# 07_LMS7002M_Power.net
KiCad netlist of a schematic drawn in Altium Designer
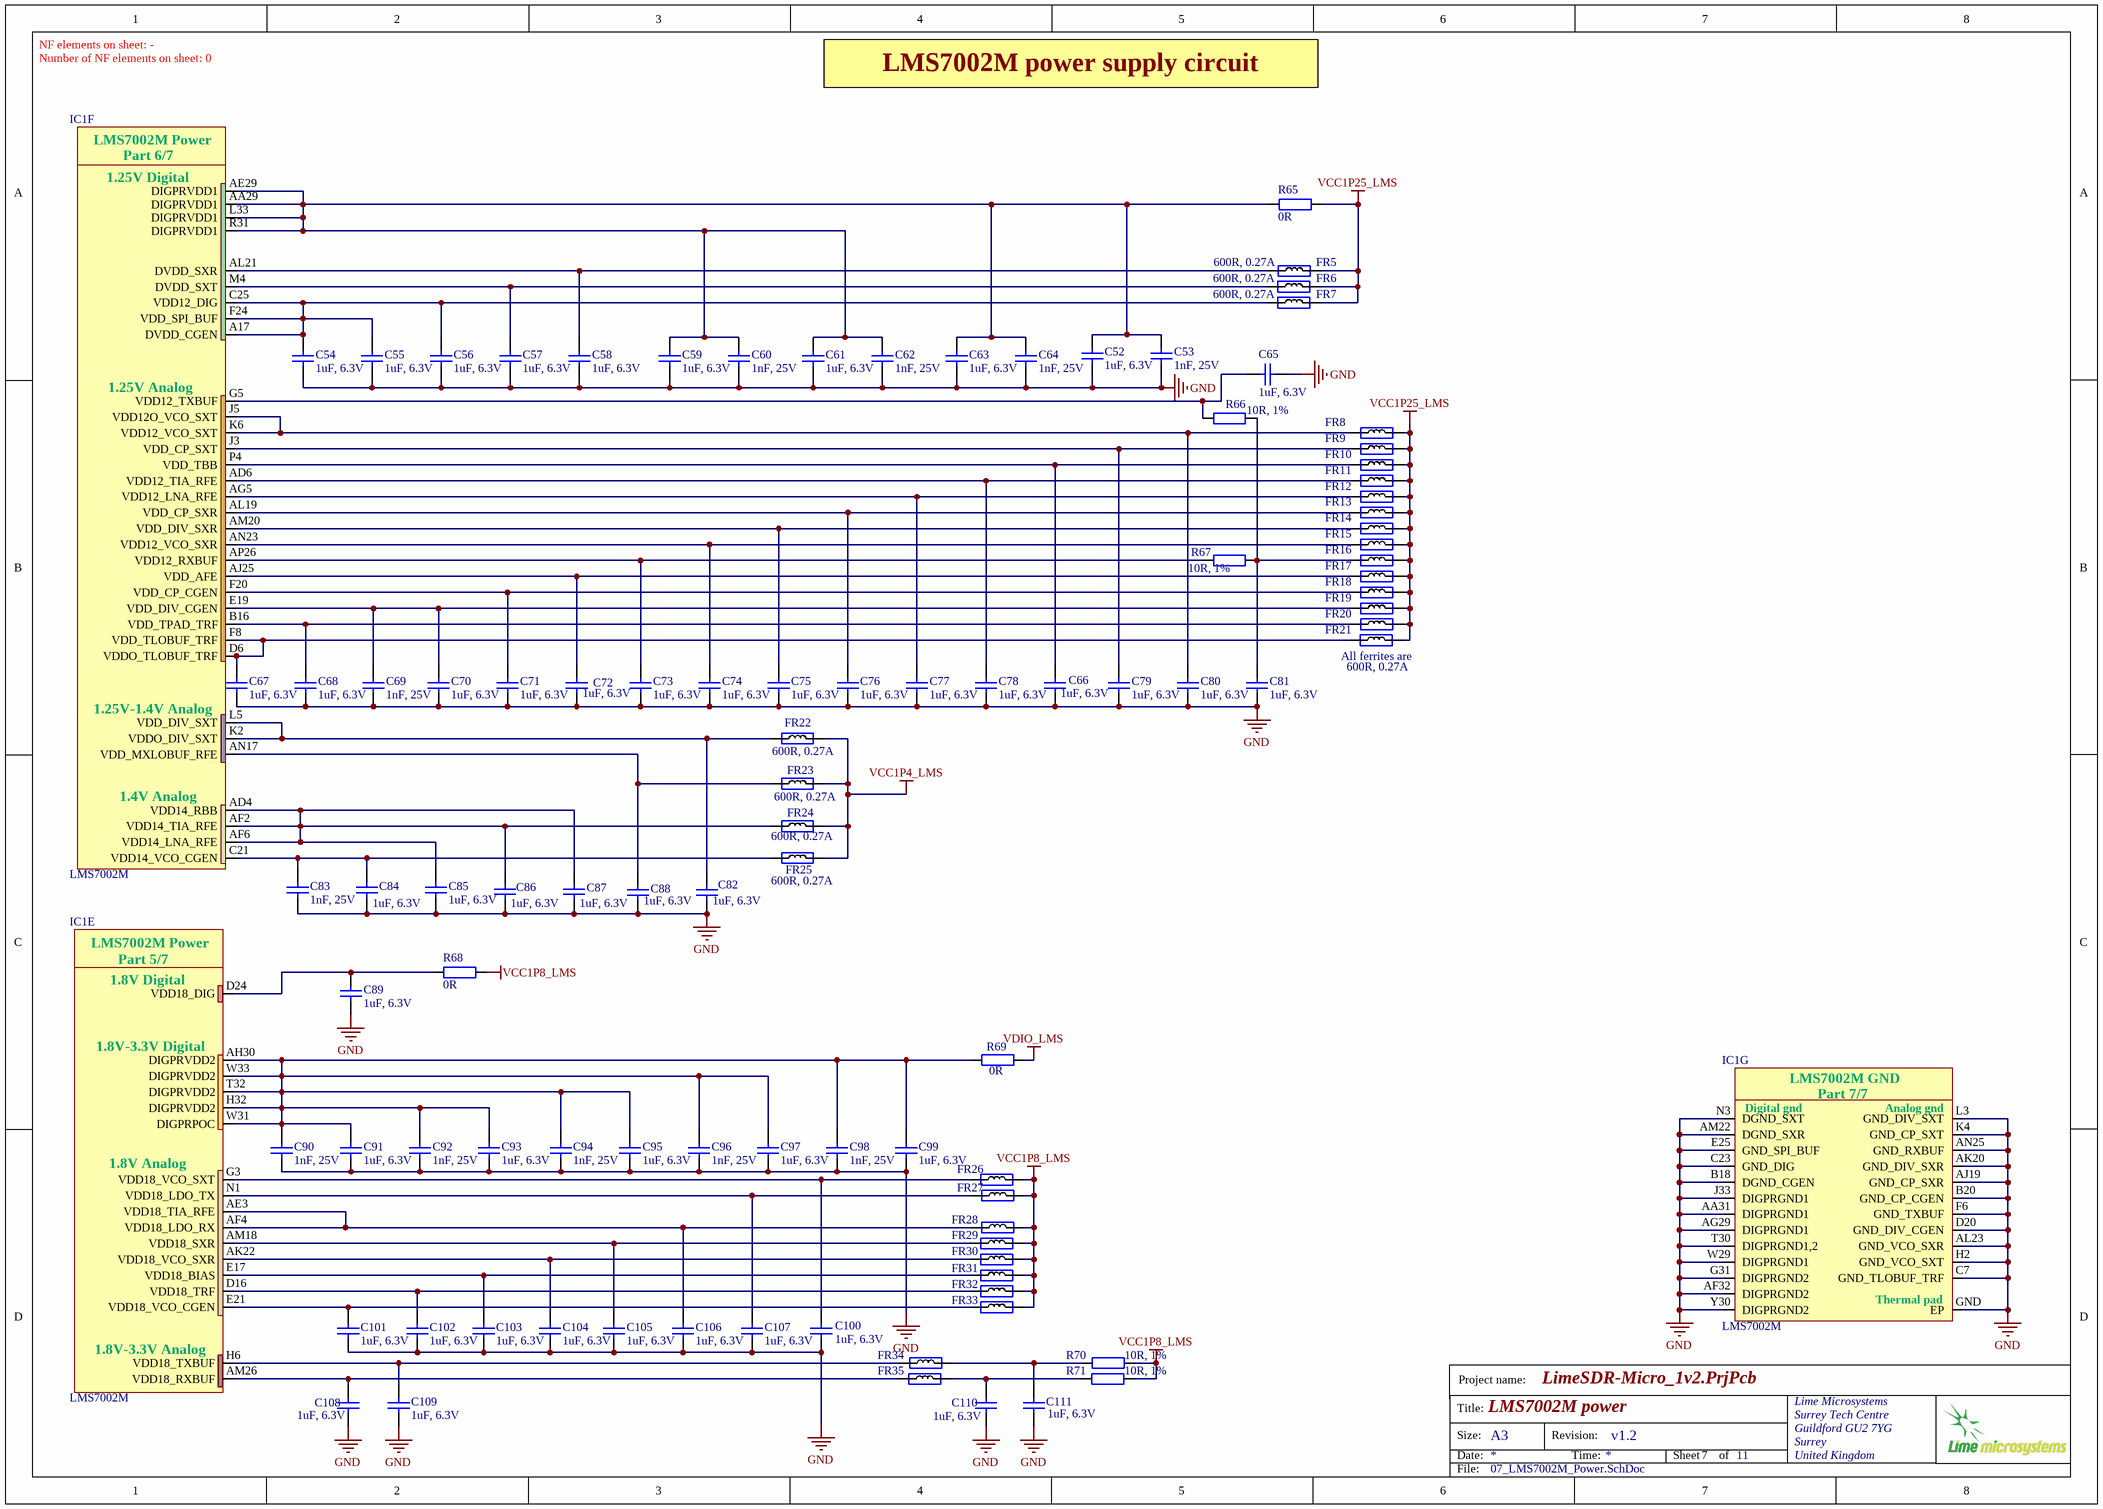
[diagram p0: 07_LMS7002M_Power.SchDoc]

(export (version "E")
  (design (tool "Eeschema 10.0.6"))
  (components
    (comp (ref "C52")
      (value "1uF, 6.3V")
      (footprint "CAP0201")
      (fields (field (name "TOLERANCE") "±20%") (field (name "MANUFACTURER") "TDK Corporation"))
      (libsource (lib "LimeMicroAltiumLib_schLib") (part "Cap_0402"))
    )
    (comp (ref "C53")
      (value "1nF, 25V")
      (footprint "CAP0201")
      (fields (field (name "TOLERANCE") "±10%") (field (name "MANUFACTURER") "TDK Corporation"))
      (libsource (lib "LimeMicroAltiumLib_schLib") (part "Cap_0402"))
    )
    (comp (ref "C54")
      (value "1uF, 6.3V")
      (footprint "CAP0201")
      (fields (field (name "TOLERANCE") "±20%") (field (name "MANUFACTURER") "TDK Corporation"))
      (libsource (lib "LimeMicroAltiumLib_schLib") (part "Cap_0402"))
    )
    (comp (ref "C55")
      (value "1uF, 6.3V")
      (footprint "CAP0201")
      (fields (field (name "TOLERANCE") "±20%") (field (name "MANUFACTURER") "TDK Corporation"))
      (libsource (lib "LimeMicroAltiumLib_schLib") (part "Cap_0402"))
    )
    (comp (ref "C56")
      (value "1uF, 6.3V")
      (footprint "CAP0201")
      (fields (field (name "TOLERANCE") "±20%") (field (name "MANUFACTURER") "TDK Corporation"))
      (libsource (lib "LimeMicroAltiumLib_schLib") (part "Cap_0402"))
    )
    (comp (ref "C57")
      (value "1uF, 6.3V")
      (footprint "CAP0201")
      (fields (field (name "TOLERANCE") "±20%") (field (name "MANUFACTURER") "TDK Corporation"))
      (libsource (lib "LimeMicroAltiumLib_schLib") (part "Cap_0402"))
    )
    (comp (ref "C58")
      (value "1uF, 6.3V")
      (footprint "CAP0201")
      (fields (field (name "TOLERANCE") "±20%") (field (name "MANUFACTURER") "TDK Corporation"))
      (libsource (lib "LimeMicroAltiumLib_schLib") (part "Cap_0402"))
    )
    (comp (ref "C59")
      (value "1uF, 6.3V")
      (footprint "CAP0201")
      (fields (field (name "TOLERANCE") "±20%") (field (name "MANUFACTURER") "TDK Corporation"))
      (libsource (lib "LimeMicroAltiumLib_schLib") (part "Cap_0402"))
    )
    (comp (ref "C60")
      (value "1nF, 25V")
      (footprint "CAP0201")
      (fields (field (name "TOLERANCE") "±10%") (field (name "MANUFACTURER") "TDK Corporation"))
      (libsource (lib "LimeMicroAltiumLib_schLib") (part "Cap_0402"))
    )
    (comp (ref "C61")
      (value "1uF, 6.3V")
      (footprint "CAP0201")
      (fields (field (name "TOLERANCE") "±20%") (field (name "MANUFACTURER") "TDK Corporation"))
      (libsource (lib "LimeMicroAltiumLib_schLib") (part "Cap_0402"))
    )
    (comp (ref "C62")
      (value "1nF, 25V")
      (footprint "CAP0201")
      (fields (field (name "TOLERANCE") "±10%") (field (name "MANUFACTURER") "TDK Corporation"))
      (libsource (lib "LimeMicroAltiumLib_schLib") (part "Cap_0402"))
    )
    (comp (ref "C63")
      (value "1uF, 6.3V")
      (footprint "CAP0201")
      (fields (field (name "TOLERANCE") "±20%") (field (name "MANUFACTURER") "TDK Corporation"))
      (libsource (lib "LimeMicroAltiumLib_schLib") (part "Cap_0402"))
    )
    (comp (ref "C64")
      (value "1nF, 25V")
      (footprint "CAP0201")
      (fields (field (name "TOLERANCE") "±10%") (field (name "MANUFACTURER") "TDK Corporation"))
      (libsource (lib "LimeMicroAltiumLib_schLib") (part "Cap_0402"))
    )
    (comp (ref "C65")
      (value "1uF, 6.3V")
      (footprint "CAP0201")
      (fields (field (name "TOLERANCE") "±20%") (field (name "MANUFACTURER") "TDK Corporation"))
      (libsource (lib "LimeMicroAltiumLib_schLib") (part "Cap_0402"))
    )
    (comp (ref "C66")
      (value "1uF, 6.3V")
      (footprint "CAP0201")
      (fields (field (name "TOLERANCE") "±20%") (field (name "MANUFACTURER") "TDK Corporation"))
      (libsource (lib "LimeMicroAltiumLib_schLib") (part "Cap_0402"))
    )
    (comp (ref "C67")
      (value "1uF, 6.3V")
      (footprint "CAP0201")
      (fields (field (name "TOLERANCE") "±20%") (field (name "MANUFACTURER") "TDK Corporation"))
      (libsource (lib "LimeMicroAltiumLib_schLib") (part "Cap_0402"))
    )
    (comp (ref "C68")
      (value "1uF, 6.3V")
      (footprint "CAP0201")
      (fields (field (name "TOLERANCE") "±20%") (field (name "MANUFACTURER") "TDK Corporation"))
      (libsource (lib "LimeMicroAltiumLib_schLib") (part "Cap_0402"))
    )
    (comp (ref "C69")
      (value "1nF, 25V")
      (footprint "CAP0201")
      (fields (field (name "TOLERANCE") "±10%") (field (name "MANUFACTURER") "TDK Corporation"))
      (libsource (lib "LimeMicroAltiumLib_schLib") (part "Cap_0402"))
    )
    (comp (ref "C70")
      (value "1uF, 6.3V")
      (footprint "CAP0201")
      (fields (field (name "TOLERANCE") "±20%") (field (name "MANUFACTURER") "TDK Corporation"))
      (libsource (lib "LimeMicroAltiumLib_schLib") (part "Cap_0402"))
    )
    (comp (ref "C71")
      (value "1uF, 6.3V")
      (footprint "CAP0201")
      (fields (field (name "TOLERANCE") "±20%") (field (name "MANUFACTURER") "TDK Corporation"))
      (libsource (lib "LimeMicroAltiumLib_schLib") (part "Cap_0402"))
    )
    (comp (ref "C72")
      (value "1uF, 6.3V")
      (footprint "CAP0201")
      (fields (field (name "TOLERANCE") "±20%") (field (name "MANUFACTURER") "TDK Corporation"))
      (libsource (lib "LimeMicroAltiumLib_schLib") (part "Cap_0402"))
    )
    (comp (ref "C73")
      (value "1uF, 6.3V")
      (footprint "CAP0201")
      (fields (field (name "TOLERANCE") "±20%") (field (name "MANUFACTURER") "TDK Corporation"))
      (libsource (lib "LimeMicroAltiumLib_schLib") (part "Cap_0402"))
    )
    (comp (ref "C74")
      (value "1uF, 6.3V")
      (footprint "CAP0201")
      (fields (field (name "TOLERANCE") "±20%") (field (name "MANUFACTURER") "TDK Corporation"))
      (libsource (lib "LimeMicroAltiumLib_schLib") (part "Cap_0402"))
    )
    (comp (ref "C75")
      (value "1uF, 6.3V")
      (footprint "CAP0201")
      (fields (field (name "TOLERANCE") "±20%") (field (name "MANUFACTURER") "TDK Corporation"))
      (libsource (lib "LimeMicroAltiumLib_schLib") (part "Cap_0402"))
    )
    (comp (ref "C76")
      (value "1uF, 6.3V")
      (footprint "CAP0201")
      (fields (field (name "TOLERANCE") "±20%") (field (name "MANUFACTURER") "TDK Corporation"))
      (libsource (lib "LimeMicroAltiumLib_schLib") (part "Cap_0402"))
    )
    (comp (ref "C77")
      (value "1uF, 6.3V")
      (footprint "CAP0201")
      (fields (field (name "TOLERANCE") "±20%") (field (name "MANUFACTURER") "TDK Corporation"))
      (libsource (lib "LimeMicroAltiumLib_schLib") (part "Cap_0402"))
    )
    (comp (ref "C78")
      (value "1uF, 6.3V")
      (footprint "CAP0201")
      (fields (field (name "TOLERANCE") "±20%") (field (name "MANUFACTURER") "TDK Corporation"))
      (libsource (lib "LimeMicroAltiumLib_schLib") (part "Cap_0402"))
    )
    (comp (ref "C79")
      (value "1uF, 6.3V")
      (footprint "CAP0201")
      (fields (field (name "TOLERANCE") "±20%") (field (name "MANUFACTURER") "TDK Corporation"))
      (libsource (lib "LimeMicroAltiumLib_schLib") (part "Cap_0402"))
    )
    (comp (ref "C80")
      (value "1uF, 6.3V")
      (footprint "CAP0201")
      (fields (field (name "TOLERANCE") "±20%") (field (name "MANUFACTURER") "TDK Corporation"))
      (libsource (lib "LimeMicroAltiumLib_schLib") (part "Cap_0402"))
    )
    (comp (ref "C81")
      (value "1uF, 6.3V")
      (footprint "CAP0201")
      (fields (field (name "TOLERANCE") "±20%") (field (name "MANUFACTURER") "TDK Corporation"))
      (libsource (lib "LimeMicroAltiumLib_schLib") (part "Cap_0402"))
    )
    (comp (ref "C82")
      (value "1uF, 6.3V")
      (footprint "CAP0201")
      (fields (field (name "TOLERANCE") "±20%") (field (name "MANUFACTURER") "TDK Corporation"))
      (libsource (lib "LimeMicroAltiumLib_schLib") (part "Cap_0402"))
    )
    (comp (ref "C83")
      (value "1nF, 25V")
      (footprint "CAP0201")
      (fields (field (name "TOLERANCE") "±10%") (field (name "MANUFACTURER") "TDK Corporation"))
      (libsource (lib "LimeMicroAltiumLib_schLib") (part "Cap_0402"))
    )
    (comp (ref "C84")
      (value "1uF, 6.3V")
      (footprint "CAP0201")
      (fields (field (name "TOLERANCE") "±20%") (field (name "MANUFACTURER") "TDK Corporation"))
      (libsource (lib "LimeMicroAltiumLib_schLib") (part "Cap_0402"))
    )
    (comp (ref "C85")
      (value "1uF, 6.3V")
      (footprint "CAP0201")
      (fields (field (name "TOLERANCE") "±20%") (field (name "MANUFACTURER") "TDK Corporation"))
      (libsource (lib "LimeMicroAltiumLib_schLib") (part "Cap_0402"))
    )
    (comp (ref "C86")
      (value "1uF, 6.3V")
      (footprint "CAP0201")
      (fields (field (name "TOLERANCE") "±20%") (field (name "MANUFACTURER") "TDK Corporation"))
      (libsource (lib "LimeMicroAltiumLib_schLib") (part "Cap_0402"))
    )
    (comp (ref "C87")
      (value "1uF, 6.3V")
      (footprint "CAP0201")
      (fields (field (name "TOLERANCE") "±20%") (field (name "MANUFACTURER") "TDK Corporation"))
      (libsource (lib "LimeMicroAltiumLib_schLib") (part "Cap_0402"))
    )
    (comp (ref "C88")
      (value "1uF, 6.3V")
      (footprint "CAP0201")
      (fields (field (name "TOLERANCE") "±20%") (field (name "MANUFACTURER") "TDK Corporation"))
      (libsource (lib "LimeMicroAltiumLib_schLib") (part "Cap_0402"))
    )
    (comp (ref "C89")
      (value "1uF, 6.3V")
      (footprint "CAP0201")
      (fields (field (name "TOLERANCE") "±20%") (field (name "MANUFACTURER") "TDK Corporation"))
      (libsource (lib "LimeMicroAltiumLib_schLib") (part "Cap_0402"))
    )
    (comp (ref "C90")
      (value "1nF, 25V")
      (footprint "CAP0201")
      (fields (field (name "TOLERANCE") "±10%") (field (name "MANUFACTURER") "TDK Corporation"))
      (libsource (lib "LimeMicroAltiumLib_schLib") (part "Cap_0402"))
    )
    (comp (ref "C91")
      (value "1uF, 6.3V")
      (footprint "CAP0201")
      (fields (field (name "TOLERANCE") "±20%") (field (name "MANUFACTURER") "TDK Corporation"))
      (libsource (lib "LimeMicroAltiumLib_schLib") (part "Cap_0402"))
    )
    (comp (ref "C92")
      (value "1nF, 25V")
      (footprint "CAP0201")
      (fields (field (name "TOLERANCE") "±10%") (field (name "MANUFACTURER") "TDK Corporation"))
      (libsource (lib "LimeMicroAltiumLib_schLib") (part "Cap_0402"))
    )
    (comp (ref "C93")
      (value "1uF, 6.3V")
      (footprint "CAP0201")
      (fields (field (name "TOLERANCE") "±20%") (field (name "MANUFACTURER") "TDK Corporation"))
      (libsource (lib "LimeMicroAltiumLib_schLib") (part "Cap_0402"))
    )
    (comp (ref "C94")
      (value "1nF, 25V")
      (footprint "CAP0201")
      (fields (field (name "TOLERANCE") "±10%") (field (name "MANUFACTURER") "TDK Corporation"))
      (libsource (lib "LimeMicroAltiumLib_schLib") (part "Cap_0402"))
    )
    (comp (ref "C95")
      (value "1uF, 6.3V")
      (footprint "CAP0201")
      (fields (field (name "TOLERANCE") "±20%") (field (name "MANUFACTURER") "TDK Corporation"))
      (libsource (lib "LimeMicroAltiumLib_schLib") (part "Cap_0402"))
    )
    (comp (ref "C96")
      (value "1nF, 25V")
      (footprint "CAP0201")
      (fields (field (name "TOLERANCE") "±10%") (field (name "MANUFACTURER") "TDK Corporation"))
      (libsource (lib "LimeMicroAltiumLib_schLib") (part "Cap_0402"))
    )
    (comp (ref "C97")
      (value "1uF, 6.3V")
      (footprint "CAP0201")
      (fields (field (name "TOLERANCE") "±20%") (field (name "MANUFACTURER") "TDK Corporation"))
      (libsource (lib "LimeMicroAltiumLib_schLib") (part "Cap_0402"))
    )
    (comp (ref "C98")
      (value "1nF, 25V")
      (footprint "CAP0201")
      (fields (field (name "TOLERANCE") "±10%") (field (name "MANUFACTURER") "TDK Corporation"))
      (libsource (lib "LimeMicroAltiumLib_schLib") (part "Cap_0402"))
    )
    (comp (ref "C99")
      (value "1uF, 6.3V")
      (footprint "CAP0201")
      (fields (field (name "TOLERANCE") "±20%") (field (name "MANUFACTURER") "TDK Corporation"))
      (libsource (lib "LimeMicroAltiumLib_schLib") (part "Cap_0402"))
    )
    (comp (ref "C100")
      (value "1uF, 6.3V")
      (footprint "CAP0201")
      (fields (field (name "TOLERANCE") "±20%") (field (name "MANUFACTURER") "TDK Corporation"))
      (libsource (lib "LimeMicroAltiumLib_schLib") (part "Cap_0402"))
    )
    (comp (ref "C101")
      (value "1uF, 6.3V")
      (footprint "CAP0201")
      (fields (field (name "TOLERANCE") "±20%") (field (name "MANUFACTURER") "TDK Corporation"))
      (libsource (lib "LimeMicroAltiumLib_schLib") (part "Cap_0402"))
    )
    (comp (ref "C102")
      (value "1uF, 6.3V")
      (footprint "CAP0201")
      (fields (field (name "TOLERANCE") "±20%") (field (name "MANUFACTURER") "TDK Corporation"))
      (libsource (lib "LimeMicroAltiumLib_schLib") (part "Cap_0402"))
    )
    (comp (ref "C103")
      (value "1uF, 6.3V")
      (footprint "CAP0201")
      (fields (field (name "TOLERANCE") "±20%") (field (name "MANUFACTURER") "TDK Corporation"))
      (libsource (lib "LimeMicroAltiumLib_schLib") (part "Cap_0402"))
    )
    (comp (ref "C104")
      (value "1uF, 6.3V")
      (footprint "CAP0201")
      (fields (field (name "TOLERANCE") "±20%") (field (name "MANUFACTURER") "TDK Corporation"))
      (libsource (lib "LimeMicroAltiumLib_schLib") (part "Cap_0402"))
    )
    (comp (ref "C105")
      (value "1uF, 6.3V")
      (footprint "CAP0201")
      (fields (field (name "TOLERANCE") "±20%") (field (name "MANUFACTURER") "TDK Corporation"))
      (libsource (lib "LimeMicroAltiumLib_schLib") (part "Cap_0402"))
    )
    (comp (ref "C106")
      (value "1uF, 6.3V")
      (footprint "CAP0201")
      (fields (field (name "TOLERANCE") "±20%") (field (name "MANUFACTURER") "TDK Corporation"))
      (libsource (lib "LimeMicroAltiumLib_schLib") (part "Cap_0402"))
    )
    (comp (ref "C107")
      (value "1uF, 6.3V")
      (footprint "CAP0201")
      (fields (field (name "TOLERANCE") "±20%") (field (name "MANUFACTURER") "TDK Corporation"))
      (libsource (lib "LimeMicroAltiumLib_schLib") (part "Cap_0402"))
    )
    (comp (ref "C108")
      (value "1uF, 6.3V")
      (footprint "CAP0201")
      (fields (field (name "TOLERANCE") "±20%") (field (name "MANUFACTURER") "TDK Corporation"))
      (libsource (lib "LimeMicroAltiumLib_schLib") (part "Cap_0402"))
    )
    (comp (ref "C109")
      (value "1uF, 6.3V")
      (footprint "CAP0201")
      (fields (field (name "TOLERANCE") "±20%") (field (name "MANUFACTURER") "TDK Corporation"))
      (libsource (lib "LimeMicroAltiumLib_schLib") (part "Cap_0402"))
    )
    (comp (ref "C110")
      (value "1uF, 6.3V")
      (footprint "CAP0201")
      (fields (field (name "TOLERANCE") "±20%") (field (name "MANUFACTURER") "TDK Corporation"))
      (libsource (lib "LimeMicroAltiumLib_schLib") (part "Cap_0402"))
    )
    (comp (ref "C111")
      (value "1uF, 6.3V")
      (footprint "CAP0201")
      (fields (field (name "TOLERANCE") "±20%") (field (name "MANUFACTURER") "TDK Corporation"))
      (libsource (lib "LimeMicroAltiumLib_schLib") (part "Cap_0402"))
    )
    (comp (ref "FR5")
      (value "600R, 0.27A")
      (footprint "RES0201")
      (fields (field (name "MANUFACTURER") "Taiyo Yuden"))
      (libsource (lib "LimeMicroAltiumLib_schLib") (part "Ferrite"))
    )
    (comp (ref "FR6")
      (value "600R, 0.27A")
      (footprint "RES0201")
      (fields (field (name "MANUFACTURER") "Taiyo Yuden"))
      (libsource (lib "LimeMicroAltiumLib_schLib") (part "Ferrite"))
    )
    (comp (ref "FR7")
      (value "600R, 0.27A")
      (footprint "RES0201")
      (fields (field (name "MANUFACTURER") "Taiyo Yuden"))
      (libsource (lib "LimeMicroAltiumLib_schLib") (part "Ferrite"))
    )
    (comp (ref "FR8")
      (value "600R, 0.27A")
      (footprint "RES0201")
      (fields (field (name "MANUFACTURER") "Taiyo Yuden"))
      (libsource (lib "LimeMicroAltiumLib_schLib") (part "Ferrite"))
    )
    (comp (ref "FR9")
      (value "600R, 0.27A")
      (footprint "RES0201")
      (fields (field (name "MANUFACTURER") "Taiyo Yuden"))
      (libsource (lib "LimeMicroAltiumLib_schLib") (part "Ferrite"))
    )
    (comp (ref "FR10")
      (value "600R, 0.27A")
      (footprint "RES0201")
      (fields (field (name "MANUFACTURER") "Taiyo Yuden"))
      (libsource (lib "LimeMicroAltiumLib_schLib") (part "Ferrite"))
    )
    (comp (ref "FR11")
      (value "600R, 0.27A")
      (footprint "RES0201")
      (fields (field (name "MANUFACTURER") "Taiyo Yuden"))
      (libsource (lib "LimeMicroAltiumLib_schLib") (part "Ferrite"))
    )
    (comp (ref "FR12")
      (value "600R, 0.27A")
      (footprint "RES0201")
      (fields (field (name "MANUFACTURER") "Taiyo Yuden"))
      (libsource (lib "LimeMicroAltiumLib_schLib") (part "Ferrite"))
    )
    (comp (ref "FR13")
      (value "600R, 0.27A")
      (footprint "RES0201")
      (fields (field (name "MANUFACTURER") "Taiyo Yuden"))
      (libsource (lib "LimeMicroAltiumLib_schLib") (part "Ferrite"))
    )
    (comp (ref "FR14")
      (value "600R, 0.27A")
      (footprint "RES0201")
      (fields (field (name "MANUFACTURER") "Taiyo Yuden"))
      (libsource (lib "LimeMicroAltiumLib_schLib") (part "Ferrite"))
    )
    (comp (ref "FR15")
      (value "600R, 0.27A")
      (footprint "RES0201")
      (fields (field (name "MANUFACTURER") "Taiyo Yuden"))
      (libsource (lib "LimeMicroAltiumLib_schLib") (part "Ferrite"))
    )
    (comp (ref "FR16")
      (value "600R, 0.27A")
      (footprint "RES0201")
      (fields (field (name "MANUFACTURER") "Taiyo Yuden"))
      (libsource (lib "LimeMicroAltiumLib_schLib") (part "Ferrite"))
    )
    (comp (ref "FR17")
      (value "600R, 0.27A")
      (footprint "RES0201")
      (fields (field (name "MANUFACTURER") "Taiyo Yuden"))
      (libsource (lib "LimeMicroAltiumLib_schLib") (part "Ferrite"))
    )
    (comp (ref "FR18")
      (value "600R, 0.27A")
      (footprint "RES0201")
      (fields (field (name "MANUFACTURER") "Taiyo Yuden"))
      (libsource (lib "LimeMicroAltiumLib_schLib") (part "Ferrite"))
    )
    (comp (ref "FR19")
      (value "600R, 0.27A")
      (footprint "RES0201")
      (fields (field (name "MANUFACTURER") "Taiyo Yuden"))
      (libsource (lib "LimeMicroAltiumLib_schLib") (part "Ferrite"))
    )
    (comp (ref "FR20")
      (value "600R, 0.27A")
      (footprint "RES0201")
      (fields (field (name "MANUFACTURER") "Taiyo Yuden"))
      (libsource (lib "LimeMicroAltiumLib_schLib") (part "Ferrite"))
    )
    (comp (ref "FR21")
      (value "600R, 0.27A")
      (footprint "RES0201")
      (fields (field (name "MANUFACTURER") "Taiyo Yuden"))
      (libsource (lib "LimeMicroAltiumLib_schLib") (part "Ferrite"))
    )
    (comp (ref "FR22")
      (value "600R, 0.27A")
      (footprint "RES0201")
      (fields (field (name "MANUFACTURER") "Taiyo Yuden"))
      (libsource (lib "LimeMicroAltiumLib_schLib") (part "Ferrite"))
    )
    (comp (ref "FR23")
      (value "600R, 0.27A")
      (footprint "RES0201")
      (fields (field (name "MANUFACTURER") "Taiyo Yuden"))
      (libsource (lib "LimeMicroAltiumLib_schLib") (part "Ferrite"))
    )
    (comp (ref "FR24")
      (value "600R, 0.27A")
      (footprint "RES0201")
      (fields (field (name "MANUFACTURER") "Taiyo Yuden"))
      (libsource (lib "LimeMicroAltiumLib_schLib") (part "Ferrite"))
    )
    (comp (ref "FR25")
      (value "600R, 0.27A")
      (footprint "RES0201")
      (fields (field (name "MANUFACTURER") "Taiyo Yuden"))
      (libsource (lib "LimeMicroAltiumLib_schLib") (part "Ferrite"))
    )
    (comp (ref "FR26")
      (value "600R, 0.27A")
      (footprint "RES0201")
      (fields (field (name "MANUFACTURER") "Taiyo Yuden"))
      (libsource (lib "LimeMicroAltiumLib_schLib") (part "Ferrite"))
    )
    (comp (ref "FR27")
      (value "600R, 0.27A")
      (footprint "RES0201")
      (fields (field (name "MANUFACTURER") "Taiyo Yuden"))
      (libsource (lib "") (part "Ferrite_1"))
    )
    (comp (ref "FR28")
      (value "600R, 0.27A")
      (footprint "RES0201")
      (fields (field (name "MANUFACTURER") "Taiyo Yuden"))
      (libsource (lib "") (part "Ferrite_1"))
    )
    (comp (ref "FR29")
      (value "600R, 0.27A")
      (footprint "RES0201")
      (fields (field (name "MANUFACTURER") "Taiyo Yuden"))
      (libsource (lib "LimeMicroAltiumLib_schLib") (part "Ferrite"))
    )
    (comp (ref "FR30")
      (value "600R, 0.27A")
      (footprint "RES0201")
      (fields (field (name "MANUFACTURER") "Taiyo Yuden"))
      (libsource (lib "LimeMicroAltiumLib_schLib") (part "Ferrite"))
    )
    (comp (ref "FR31")
      (value "600R, 0.27A")
      (footprint "RES0201")
      (fields (field (name "MANUFACTURER") "Taiyo Yuden"))
      (libsource (lib "LimeMicroAltiumLib_schLib") (part "Ferrite"))
    )
    (comp (ref "FR32")
      (value "600R, 0.27A")
      (footprint "RES0201")
      (fields (field (name "MANUFACTURER") "Taiyo Yuden"))
      (libsource (lib "LimeMicroAltiumLib_schLib") (part "Ferrite"))
    )
    (comp (ref "FR33")
      (value "600R, 0.27A")
      (footprint "RES0201")
      (fields (field (name "MANUFACTURER") "Taiyo Yuden"))
      (libsource (lib "LimeMicroAltiumLib_schLib") (part "Ferrite"))
    )
    (comp (ref "FR34")
      (value "600R, 0.27A")
      (footprint "RES0201")
      (fields (field (name "MANUFACTURER") "Taiyo Yuden"))
      (libsource (lib "") (part "Ferrite_1"))
    )
    (comp (ref "FR35")
      (value "600R, 0.27A")
      (footprint "RES0201")
      (fields (field (name "MANUFACTURER") "Taiyo Yuden"))
      (libsource (lib "LimeMicroAltiumLib_schLib") (part "Ferrite"))
    )
    (comp (ref "IC1")
      (value "LMS7002M")
      (footprint "LMS7002M_v5_LESS_SILK")
      (description "Schematic symbol revision 4. Default footprint - 0.31mm pad")
      (fields (field (name "MANUFACTURER") "Lime Microsystems"))
      (libsource (lib "LimeMicroAltiumLib_schLib_r04") (part "LMS7002Mr4"))
    )
    (comp (ref "R65")
      (value "0R")
      (footprint "RES0402")
      (fields (field (name "MANUFACTURER") "Yageo") (field (name "TOLERANCE") "Jumper"))
      (libsource (lib "LimeMicroAltiumLib_schLib") (part "Res_0402"))
    )
    (comp (ref "R66")
      (value "10R, 1%")
      (footprint "RES0201")
      (fields
        (field (name "MANUFACTURER") "Panasonic Electronic Components")
        (field (name "TOLERANCE") "±1%")
      )
      (libsource (lib "LimeMicroAltiumLib_schLib") (part "Res_0402"))
    )
    (comp (ref "R67")
      (value "10R, 1%")
      (footprint "RES0201")
      (fields
        (field (name "MANUFACTURER") "Panasonic Electronic Components")
        (field (name "TOLERANCE") "±1%")
      )
      (libsource (lib "LimeMicroAltiumLib_schLib") (part "Res_0402"))
    )
    (comp (ref "R68")
      (value "0R")
      (footprint "RES0201")
      (fields (field (name "MANUFACTURER") "Yageo") (field (name "TOLERANCE") "5%"))
      (libsource (lib "LimeMicroAltiumLib_schLib") (part "Res_0402"))
    )
    (comp (ref "R69")
      (value "0R")
      (footprint "RES0402")
      (fields (field (name "MANUFACTURER") "Yageo") (field (name "TOLERANCE") "Jumper"))
      (libsource (lib "LimeMicroAltiumLib_schLib") (part "Res_0402"))
    )
    (comp (ref "R70")
      (value "10R, 1%")
      (footprint "RES0201")
      (fields
        (field (name "MANUFACTURER") "Panasonic Electronic Components")
        (field (name "TOLERANCE") "±1%")
      )
      (libsource (lib "LimeMicroAltiumLib_schLib") (part "Res_0402"))
    )
    (comp (ref "R71")
      (value "10R, 1%")
      (footprint "RES0201")
      (fields
        (field (name "MANUFACTURER") "Panasonic Electronic Components")
        (field (name "TOLERANCE") "±1%")
      )
      (libsource (lib "LimeMicroAltiumLib_schLib") (part "Res_0402"))
    )
  )
  (nets
    (net (code "1") (name "GND") (class "Default")
      (node (ref "C100") (pin "2") (pinfunction "2_2") (pintype "passive"))
      (node (ref "C101") (pin "2") (pinfunction "2_2") (pintype "passive"))
      (node (ref "C102") (pin "2") (pinfunction "2_2") (pintype "passive"))
      (node (ref "C103") (pin "2") (pinfunction "2_2") (pintype "passive"))
      (node (ref "C104") (pin "2") (pinfunction "2_2") (pintype "passive"))
      (node (ref "C105") (pin "2") (pinfunction "2_2") (pintype "passive"))
      (node (ref "C106") (pin "2") (pinfunction "2_2") (pintype "passive"))
      (node (ref "C107") (pin "2") (pinfunction "2_2") (pintype "passive"))
      (node (ref "C108") (pin "2") (pinfunction "2_2") (pintype "passive"))
      (node (ref "C109") (pin "2") (pinfunction "2_2") (pintype "passive"))
      (node (ref "C110") (pin "2") (pinfunction "2_2") (pintype "passive"))
      (node (ref "C111") (pin "2") (pinfunction "2_2") (pintype "passive"))
      (node (ref "C52") (pin "2") (pinfunction "2_2") (pintype "passive"))
      (node (ref "C53") (pin "2") (pinfunction "2_2") (pintype "passive"))
      (node (ref "C54") (pin "2") (pinfunction "2_2") (pintype "passive"))
      (node (ref "C55") (pin "2") (pinfunction "2_2") (pintype "passive"))
      (node (ref "C56") (pin "2") (pinfunction "2_2") (pintype "passive"))
      (node (ref "C57") (pin "1") (pinfunction "1_1") (pintype "passive"))
      (node (ref "C58") (pin "2") (pinfunction "2_2") (pintype "passive"))
      (node (ref "C59") (pin "2") (pinfunction "2_2") (pintype "passive"))
      (node (ref "C60") (pin "2") (pinfunction "2_2") (pintype "passive"))
      (node (ref "C61") (pin "2") (pinfunction "2_2") (pintype "passive"))
      (node (ref "C62") (pin "2") (pinfunction "2_2") (pintype "passive"))
      (node (ref "C63") (pin "2") (pinfunction "2_2") (pintype "passive"))
      (node (ref "C64") (pin "2") (pinfunction "2_2") (pintype "passive"))
      (node (ref "C65") (pin "2") (pinfunction "2_2") (pintype "passive"))
      (node (ref "C66") (pin "2") (pinfunction "2_2") (pintype "passive"))
      (node (ref "C67") (pin "2") (pinfunction "2_2") (pintype "passive"))
      (node (ref "C68") (pin "2") (pinfunction "2_2") (pintype "passive"))
      (node (ref "C69") (pin "2") (pinfunction "2_2") (pintype "passive"))
      (node (ref "C70") (pin "2") (pinfunction "2_2") (pintype "passive"))
      (node (ref "C71") (pin "1") (pinfunction "1_1") (pintype "passive"))
      (node (ref "C72") (pin "2") (pinfunction "2_2") (pintype "passive"))
      (node (ref "C73") (pin "2") (pinfunction "2_2") (pintype "passive"))
      (node (ref "C74") (pin "2") (pinfunction "2_2") (pintype "passive"))
      (node (ref "C75") (pin "2") (pinfunction "2_2") (pintype "passive"))
      (node (ref "C76") (pin "2") (pinfunction "2_2") (pintype "passive"))
      (node (ref "C77") (pin "2") (pinfunction "2_2") (pintype "passive"))
      (node (ref "C78") (pin "1") (pinfunction "1_1") (pintype "passive"))
      (node (ref "C79") (pin "2") (pinfunction "2_2") (pintype "passive"))
      (node (ref "C80") (pin "1") (pinfunction "1_1") (pintype "passive"))
      (node (ref "C81") (pin "1") (pinfunction "1_1") (pintype "passive"))
      (node (ref "C82") (pin "2") (pinfunction "2_2") (pintype "passive"))
      (node (ref "C83") (pin "2") (pinfunction "2_2") (pintype "passive"))
      (node (ref "C84") (pin "2") (pinfunction "2_2") (pintype "passive"))
      (node (ref "C85") (pin "2") (pinfunction "2_2") (pintype "passive"))
      (node (ref "C86") (pin "2") (pinfunction "2_2") (pintype "passive"))
      (node (ref "C87") (pin "2") (pinfunction "2_2") (pintype "passive"))
      (node (ref "C88") (pin "2") (pinfunction "2_2") (pintype "passive"))
      (node (ref "C89") (pin "2") (pinfunction "2_2") (pintype "passive"))
      (node (ref "C90") (pin "2") (pinfunction "2_2") (pintype "passive"))
      (node (ref "C91") (pin "2") (pinfunction "2_2") (pintype "passive"))
      (node (ref "C92") (pin "2") (pinfunction "2_2") (pintype "passive"))
      (node (ref "C93") (pin "2") (pinfunction "2_2") (pintype "passive"))
      (node (ref "C94") (pin "2") (pinfunction "2_2") (pintype "passive"))
      (node (ref "C95") (pin "2") (pinfunction "2_2") (pintype "passive"))
      (node (ref "C96") (pin "2") (pinfunction "2_2") (pintype "passive"))
      (node (ref "C97") (pin "2") (pinfunction "2_2") (pintype "passive"))
      (node (ref "C98") (pin "2") (pinfunction "2_2") (pintype "passive"))
      (node (ref "C99") (pin "2") (pinfunction "2_2") (pintype "passive"))
      (node (ref "IC1") (pin "AA31") (pinfunction "DIGPRGND1_AA31") (pintype "passive"))
      (node (ref "IC1") (pin "AF32") (pinfunction "DIGPRGND2_AF32") (pintype "passive"))
      (node (ref "IC1") (pin "AG29") (pinfunction "DIGPRGND1_AG29") (pintype "passive"))
      (node (ref "IC1") (pin "AJ19") (pinfunction "GND_CP_SXR_AJ19") (pintype "passive"))
      (node (ref "IC1") (pin "AK20") (pinfunction "GND_DIV_SXR_AK20") (pintype "passive"))
      (node (ref "IC1") (pin "AL23") (pinfunction "GND_VCO_SXR_AL23") (pintype "passive"))
      (node (ref "IC1") (pin "AM22") (pinfunction "DGND_SXR_AM22") (pintype "passive"))
      (node (ref "IC1") (pin "AN25") (pinfunction "GND_RXBUF_AN25") (pintype "passive"))
      (node (ref "IC1") (pin "B18") (pinfunction "DGND_CGEN_B18") (pintype "passive"))
      (node (ref "IC1") (pin "B20") (pinfunction "GND_CP_CGEN_B20") (pintype "passive"))
      (node (ref "IC1") (pin "C23") (pinfunction "GND_DIG_C23") (pintype "passive"))
      (node (ref "IC1") (pin "C7") (pinfunction "GND_TLOBUF_TRF_C7") (pintype "passive"))
      (node (ref "IC1") (pin "D20") (pinfunction "GND_DIV_CGEN_D20") (pintype "passive"))
      (node (ref "IC1") (pin "E25") (pinfunction "GND_SPI_BUF_E25") (pintype "passive"))
      (node (ref "IC1") (pin "F6") (pinfunction "GND_TXBUF_F6") (pintype "passive"))
      (node (ref "IC1") (pin "G31") (pinfunction "DIGPRGND2_G31") (pintype "passive"))
      (node (ref "IC1") (pin "GND") (pinfunction "EP_GND") (pintype "passive"))
      (node (ref "IC1") (pin "H2") (pinfunction "GND_VCO_SXT_H2") (pintype "passive"))
      (node (ref "IC1") (pin "J33") (pinfunction "DIGPRGND1_J33") (pintype "passive"))
      (node (ref "IC1") (pin "K4") (pinfunction "GND_CP_SXT_K4") (pintype "passive"))
      (node (ref "IC1") (pin "L3") (pinfunction "GND_DIV_SXT_L3") (pintype "passive"))
      (node (ref "IC1") (pin "N3") (pinfunction "DGND_SXT_N3") (pintype "passive"))
      (node (ref "IC1") (pin "T30") (pinfunction "DIGPRGND1,2_T30") (pintype "passive"))
      (node (ref "IC1") (pin "W29") (pinfunction "DIGPRGND1_W29") (pintype "passive"))
      (node (ref "IC1") (pin "Y30") (pinfunction "DIGPRGND2_Y30") (pintype "passive"))
    )
    (net (code "2") (name "Net-(C52-Pad1)") (class "Default")
      (node (ref "C52") (pin "1") (pinfunction "1_1") (pintype "passive"))
      (node (ref "C53") (pin "1") (pinfunction "1_1") (pintype "passive"))
      (node (ref "C59") (pin "1") (pinfunction "1_1") (pintype "passive"))
      (node (ref "C60") (pin "1") (pinfunction "1_1") (pintype "passive"))
      (node (ref "C61") (pin "1") (pinfunction "1_1") (pintype "passive"))
      (node (ref "C62") (pin "1") (pinfunction "1_1") (pintype "passive"))
      (node (ref "C63") (pin "1") (pinfunction "1_1") (pintype "passive"))
      (node (ref "C64") (pin "1") (pinfunction "1_1") (pintype "passive"))
      (node (ref "IC1") (pin "AA29") (pinfunction "DIGPRVDD1_AA29") (pintype "power_in"))
      (node (ref "IC1") (pin "AE29") (pinfunction "DIGPRVDD1_AE29") (pintype "power_in"))
      (node (ref "IC1") (pin "L33") (pinfunction "DIGPRVDD1_L33") (pintype "power_in"))
      (node (ref "IC1") (pin "R31") (pinfunction "DIGPRVDD1_R31") (pintype "power_in"))
      (node (ref "R65") (pin "2") (pinfunction "2_2") (pintype "passive"))
    )
    (net (code "3") (name "Net-(C81-Pad2)") (class "Default")
      (node (ref "C81") (pin "2") (pinfunction "2_2") (pintype "passive"))
      (node (ref "FR16") (pin "1") (pinfunction "1_1") (pintype "passive"))
      (node (ref "R66") (pin "2") (pinfunction "2_2") (pintype "passive"))
      (node (ref "R67") (pin "2") (pinfunction "2_2") (pintype "passive"))
    )
    (net (code "4") (name "Net-(C110-Pad1)") (class "Default")
      (node (ref "C110") (pin "1") (pinfunction "1_1") (pintype "passive"))
      (node (ref "FR35") (pin "2") (pinfunction "2_2") (pintype "passive"))
      (node (ref "R71") (pin "2") (pinfunction "2_2") (pintype "passive"))
    )
    (net (code "5") (name "Net-(C111-Pad1)") (class "Default")
      (node (ref "C111") (pin "1") (pinfunction "1_1") (pintype "passive"))
      (node (ref "FR34") (pin "1") (pinfunction "1_1") (pintype "passive"))
      (node (ref "R70") (pin "1") (pinfunction "1_1") (pintype "passive"))
    )
    (net (code "6") (name "Net-(IC1E-DIGPRPOC)") (class "Default")
      (node (ref "C90") (pin "1") (pinfunction "1_1") (pintype "passive"))
      (node (ref "C91") (pin "1") (pinfunction "1_1") (pintype "passive"))
      (node (ref "C92") (pin "1") (pinfunction "1_1") (pintype "passive"))
      (node (ref "C93") (pin "1") (pinfunction "1_1") (pintype "passive"))
      (node (ref "C94") (pin "1") (pinfunction "1_1") (pintype "passive"))
      (node (ref "C95") (pin "1") (pinfunction "1_1") (pintype "passive"))
      (node (ref "C96") (pin "1") (pinfunction "1_1") (pintype "passive"))
      (node (ref "C97") (pin "1") (pinfunction "1_1") (pintype "passive"))
      (node (ref "C98") (pin "1") (pinfunction "1_1") (pintype "passive"))
      (node (ref "C99") (pin "1") (pinfunction "1_1") (pintype "passive"))
      (node (ref "IC1") (pin "AH30") (pinfunction "DIGPRVDD2_AH30") (pintype "power_in"))
      (node (ref "IC1") (pin "H32") (pinfunction "DIGPRVDD2_H32") (pintype "power_in"))
      (node (ref "IC1") (pin "T32") (pinfunction "DIGPRVDD2_T32") (pintype "power_in"))
      (node (ref "IC1") (pin "W31") (pinfunction "DIGPRPOC_W31") (pintype "power_in"))
      (node (ref "IC1") (pin "W33") (pinfunction "DIGPRVDD2_W33") (pintype "power_in"))
      (node (ref "R69") (pin "2") (pinfunction "2_2") (pintype "passive"))
    )
    (net (code "7") (name "Net-(IC1E-VDD18_BIAS)") (class "Default")
      (node (ref "C103") (pin "1") (pinfunction "1_1") (pintype "passive"))
      (node (ref "FR31") (pin "1") (pinfunction "1_1") (pintype "passive"))
      (node (ref "IC1") (pin "E17") (pinfunction "VDD18_BIAS_E17") (pintype "power_in"))
    )
    (net (code "8") (name "Net-(IC1E-VDD18_DIG)") (class "Default")
      (node (ref "C89") (pin "1") (pinfunction "1_1") (pintype "passive"))
      (node (ref "IC1") (pin "D24") (pinfunction "VDD18_DIG_D24") (pintype "power_in"))
      (node (ref "R68") (pin "1") (pinfunction "1_1") (pintype "passive"))
    )
    (net (code "9") (name "Net-(IC1E-VDD18_LDO_RX)") (class "Default")
      (node (ref "C106") (pin "1") (pinfunction "1_1") (pintype "passive"))
      (node (ref "FR28") (pin "2") (pinfunction "2_2") (pintype "passive"))
      (node (ref "IC1") (pin "AE3") (pinfunction "VDD18_TIA_RFE_AE3") (pintype "power_in"))
      (node (ref "IC1") (pin "AF4") (pinfunction "VDD18_LDO_RX_AF4") (pintype "power_in"))
    )
    (net (code "10") (name "Net-(IC1E-VDD18_LDO_TX)") (class "Default")
      (node (ref "C107") (pin "1") (pinfunction "1_1") (pintype "passive"))
      (node (ref "FR27") (pin "2") (pinfunction "2_2") (pintype "passive"))
      (node (ref "IC1") (pin "N1") (pinfunction "VDD18_LDO_TX_N1") (pintype "power_in"))
    )
    (net (code "11") (name "Net-(IC1E-VDD18_RXBUF)") (class "Default")
      (node (ref "C108") (pin "1") (pinfunction "1_1") (pintype "passive"))
      (node (ref "FR35") (pin "1") (pinfunction "1_1") (pintype "passive"))
      (node (ref "IC1") (pin "AM26") (pinfunction "VDD18_RXBUF_AM26") (pintype "power_in"))
    )
    (net (code "12") (name "Net-(IC1E-VDD18_SXR)") (class "Default")
      (node (ref "C105") (pin "1") (pinfunction "1_1") (pintype "passive"))
      (node (ref "FR29") (pin "1") (pinfunction "1_1") (pintype "passive"))
      (node (ref "IC1") (pin "AM18") (pinfunction "VDD18_SXR_AM18") (pintype "power_in"))
    )
    (net (code "13") (name "Net-(IC1E-VDD18_TRF)") (class "Default")
      (node (ref "C102") (pin "1") (pinfunction "1_1") (pintype "passive"))
      (node (ref "FR32") (pin "1") (pinfunction "1_1") (pintype "passive"))
      (node (ref "IC1") (pin "D16") (pinfunction "VDD18_TRF_D16") (pintype "power_in"))
    )
    (net (code "14") (name "Net-(IC1E-VDD18_TXBUF)") (class "Default")
      (node (ref "C109") (pin "1") (pinfunction "1_1") (pintype "passive"))
      (node (ref "FR34") (pin "2") (pinfunction "2_2") (pintype "passive"))
      (node (ref "IC1") (pin "H6") (pinfunction "VDD18_TXBUF_H6") (pintype "power_in"))
    )
    (net (code "15") (name "Net-(IC1E-VDD18_VCO_CGEN)") (class "Default")
      (node (ref "C101") (pin "1") (pinfunction "1_1") (pintype "passive"))
      (node (ref "FR33") (pin "1") (pinfunction "1_1") (pintype "passive"))
      (node (ref "IC1") (pin "E21") (pinfunction "VDD18_VCO_CGEN_E21") (pintype "power_in"))
    )
    (net (code "16") (name "Net-(IC1E-VDD18_VCO_SXR)") (class "Default")
      (node (ref "C104") (pin "1") (pinfunction "1_1") (pintype "passive"))
      (node (ref "FR30") (pin "1") (pinfunction "1_1") (pintype "passive"))
      (node (ref "IC1") (pin "AK22") (pinfunction "VDD18_VCO_SXR_AK22") (pintype "power_in"))
    )
    (net (code "17") (name "Net-(IC1E-VDD18_VCO_SXT)") (class "Default")
      (node (ref "C100") (pin "1") (pinfunction "1_1") (pintype "passive"))
      (node (ref "FR26") (pin "1") (pinfunction "1_1") (pintype "passive"))
      (node (ref "IC1") (pin "G3") (pinfunction "VDD18_VCO_SXT_G3") (pintype "power_in"))
    )
    (net (code "18") (name "Net-(IC1F-DVDD_CGEN)") (class "Default")
      (node (ref "C54") (pin "1") (pinfunction "1_1") (pintype "passive"))
      (node (ref "C55") (pin "1") (pinfunction "1_1") (pintype "passive"))
      (node (ref "C56") (pin "1") (pinfunction "1_1") (pintype "passive"))
      (node (ref "FR7") (pin "1") (pinfunction "1_1") (pintype "passive"))
      (node (ref "IC1") (pin "A17") (pinfunction "DVDD_CGEN_A17") (pintype "power_in"))
      (node (ref "IC1") (pin "C25") (pinfunction "VDD12_DIG_C25") (pintype "power_in"))
      (node (ref "IC1") (pin "F24") (pinfunction "VDD_SPI_BUF_F24") (pintype "power_in"))
    )
    (net (code "19") (name "Net-(IC1F-DVDD_SXR)") (class "Default")
      (node (ref "C58") (pin "1") (pinfunction "1_1") (pintype "passive"))
      (node (ref "FR5") (pin "1") (pinfunction "1_1") (pintype "passive"))
      (node (ref "IC1") (pin "AL21") (pinfunction "DVDD_SXR_AL21") (pintype "power_in"))
    )
    (net (code "20") (name "Net-(IC1F-DVDD_SXT)") (class "Default")
      (node (ref "C57") (pin "2") (pinfunction "2_2") (pintype "passive"))
      (node (ref "FR6") (pin "1") (pinfunction "1_1") (pintype "passive"))
      (node (ref "IC1") (pin "M4") (pinfunction "DVDD_SXT_M4") (pintype "power_in"))
    )
    (net (code "21") (name "Net-(IC1F-VDD12O_VCO_SXT)") (class "Default")
      (node (ref "C80") (pin "2") (pinfunction "2_2") (pintype "passive"))
      (node (ref "FR8") (pin "1") (pinfunction "1_1") (pintype "passive"))
      (node (ref "IC1") (pin "J5") (pinfunction "VDD12O_VCO_SXT_J5") (pintype "power_in"))
      (node (ref "IC1") (pin "K6") (pinfunction "VDD12_VCO_SXT_K6") (pintype "power_in"))
    )
    (net (code "22") (name "Net-(IC1F-VDD12_LNA_RFE)") (class "Default")
      (node (ref "C77") (pin "1") (pinfunction "1_1") (pintype "passive"))
      (node (ref "FR12") (pin "1") (pinfunction "1_1") (pintype "passive"))
      (node (ref "IC1") (pin "AG5") (pinfunction "VDD12_LNA_RFE_AG5") (pintype "power_in"))
    )
    (net (code "23") (name "Net-(IC1F-VDD12_RXBUF)") (class "Default")
      (node (ref "C73") (pin "1") (pinfunction "1_1") (pintype "passive"))
      (node (ref "IC1") (pin "AP26") (pinfunction "VDD12_RXBUF_AP26") (pintype "power_in"))
      (node (ref "R67") (pin "1") (pinfunction "1_1") (pintype "passive"))
    )
    (net (code "24") (name "Net-(IC1F-VDD12_TIA_RFE)") (class "Default")
      (node (ref "C78") (pin "2") (pinfunction "2_2") (pintype "passive"))
      (node (ref "FR11") (pin "1") (pinfunction "1_1") (pintype "passive"))
      (node (ref "IC1") (pin "AD6") (pinfunction "VDD12_TIA_RFE_AD6") (pintype "power_in"))
    )
    (net (code "25") (name "Net-(IC1F-VDD12_TXBUF)") (class "Default")
      (node (ref "C65") (pin "1") (pinfunction "1_1") (pintype "passive"))
      (node (ref "IC1") (pin "G5") (pinfunction "VDD12_TXBUF_G5") (pintype "power_in"))
      (node (ref "R66") (pin "1") (pinfunction "1_1") (pintype "passive"))
    )
    (net (code "26") (name "Net-(IC1F-VDD12_VCO_SXR)") (class "Default")
      (node (ref "C74") (pin "1") (pinfunction "1_1") (pintype "passive"))
      (node (ref "FR15") (pin "1") (pinfunction "1_1") (pintype "passive"))
      (node (ref "IC1") (pin "AN23") (pinfunction "VDD12_VCO_SXR_AN23") (pintype "power_in"))
    )
    (net (code "27") (name "Net-(IC1F-VDD14_LNA_RFE)") (class "Default")
      (node (ref "C85") (pin "1") (pinfunction "1_1") (pintype "passive"))
      (node (ref "C86") (pin "1") (pinfunction "1_1") (pintype "passive"))
      (node (ref "C87") (pin "1") (pinfunction "1_1") (pintype "passive"))
      (node (ref "FR24") (pin "1") (pinfunction "1_1") (pintype "passive"))
      (node (ref "IC1") (pin "AD4") (pinfunction "VDD14_RBB_AD4") (pintype "power_in"))
      (node (ref "IC1") (pin "AF2") (pinfunction "VDD14_TIA_RFE_AF2") (pintype "power_in"))
      (node (ref "IC1") (pin "AF6") (pinfunction "VDD14_LNA_RFE_AF6") (pintype "power_in"))
    )
    (net (code "28") (name "Net-(IC1F-VDD14_VCO_CGEN)") (class "Default")
      (node (ref "C83") (pin "1") (pinfunction "1_1") (pintype "passive"))
      (node (ref "C84") (pin "1") (pinfunction "1_1") (pintype "passive"))
      (node (ref "FR25") (pin "1") (pinfunction "1_1") (pintype "passive"))
      (node (ref "IC1") (pin "C21") (pinfunction "VDD14_VCO_CGEN_C21") (pintype "power_in"))
    )
    (net (code "29") (name "Net-(IC1F-VDDO_DIV_SXT)") (class "Default")
      (node (ref "C82") (pin "1") (pinfunction "1_1") (pintype "passive"))
      (node (ref "FR22") (pin "1") (pinfunction "1_1") (pintype "passive"))
      (node (ref "IC1") (pin "K2") (pinfunction "VDDO_DIV_SXT_K2") (pintype "power_in"))
      (node (ref "IC1") (pin "L5") (pinfunction "VDD_DIV_SXT_L5") (pintype "power_in"))
    )
    (net (code "30") (name "Net-(IC1F-VDDO_TLOBUF_TRF)") (class "Default")
      (node (ref "C67") (pin "1") (pinfunction "1_1") (pintype "passive"))
      (node (ref "FR21") (pin "1") (pinfunction "1_1") (pintype "passive"))
      (node (ref "IC1") (pin "D6") (pinfunction "VDDO_TLOBUF_TRF_D6") (pintype "power_in"))
      (node (ref "IC1") (pin "F8") (pinfunction "VDD_TLOBUF_TRF_F8") (pintype "power_in"))
    )
    (net (code "31") (name "Net-(IC1F-VDD_AFE)") (class "Default")
      (node (ref "C72") (pin "1") (pinfunction "1_1") (pintype "passive"))
      (node (ref "FR17") (pin "1") (pinfunction "1_1") (pintype "passive"))
      (node (ref "IC1") (pin "AJ25") (pinfunction "VDD_AFE_AJ25") (pintype "power_in"))
    )
    (net (code "32") (name "Net-(IC1F-VDD_CP_CGEN)") (class "Default")
      (node (ref "C71") (pin "2") (pinfunction "2_2") (pintype "passive"))
      (node (ref "FR18") (pin "1") (pinfunction "1_1") (pintype "passive"))
      (node (ref "IC1") (pin "F20") (pinfunction "VDD_CP_CGEN_F20") (pintype "power_in"))
    )
    (net (code "33") (name "Net-(IC1F-VDD_CP_SXR)") (class "Default")
      (node (ref "C76") (pin "1") (pinfunction "1_1") (pintype "passive"))
      (node (ref "FR13") (pin "1") (pinfunction "1_1") (pintype "passive"))
      (node (ref "IC1") (pin "AL19") (pinfunction "VDD_CP_SXR_AL19") (pintype "power_in"))
    )
    (net (code "34") (name "Net-(IC1F-VDD_CP_SXT)") (class "Default")
      (node (ref "C79") (pin "1") (pinfunction "1_1") (pintype "passive"))
      (node (ref "FR9") (pin "1") (pinfunction "1_1") (pintype "passive"))
      (node (ref "IC1") (pin "J3") (pinfunction "VDD_CP_SXT_J3") (pintype "power_in"))
    )
    (net (code "35") (name "Net-(IC1F-VDD_DIV_CGEN)") (class "Default")
      (node (ref "C69") (pin "1") (pinfunction "1_1") (pintype "passive"))
      (node (ref "C70") (pin "1") (pinfunction "1_1") (pintype "passive"))
      (node (ref "FR19") (pin "1") (pinfunction "1_1") (pintype "passive"))
      (node (ref "IC1") (pin "E19") (pinfunction "VDD_DIV_CGEN_E19") (pintype "power_in"))
    )
    (net (code "36") (name "Net-(IC1F-VDD_DIV_SXR)") (class "Default")
      (node (ref "C75") (pin "1") (pinfunction "1_1") (pintype "passive"))
      (node (ref "FR14") (pin "1") (pinfunction "1_1") (pintype "passive"))
      (node (ref "IC1") (pin "AM20") (pinfunction "VDD_DIV_SXR_AM20") (pintype "power_in"))
    )
    (net (code "37") (name "Net-(IC1F-VDD_MXLOBUF_RFE)") (class "Default")
      (node (ref "C88") (pin "1") (pinfunction "1_1") (pintype "passive"))
      (node (ref "FR23") (pin "1") (pinfunction "1_1") (pintype "passive"))
      (node (ref "IC1") (pin "AN17") (pinfunction "VDD_MXLOBUF_RFE_AN17") (pintype "power_in"))
    )
    (net (code "38") (name "Net-(IC1F-VDD_TBB)") (class "Default")
      (node (ref "C66") (pin "1") (pinfunction "1_1") (pintype "passive"))
      (node (ref "FR10") (pin "1") (pinfunction "1_1") (pintype "passive"))
      (node (ref "IC1") (pin "P4") (pinfunction "VDD_TBB_P4") (pintype "power_in"))
    )
    (net (code "39") (name "Net-(IC1F-VDD_TPAD_TRF)") (class "Default")
      (node (ref "C68") (pin "1") (pinfunction "1_1") (pintype "passive"))
      (node (ref "FR20") (pin "1") (pinfunction "1_1") (pintype "passive"))
      (node (ref "IC1") (pin "B16") (pinfunction "VDD_TPAD_TRF_B16") (pintype "power_in"))
    )
    (net (code "40") (name "VCC1P4_LMS") (class "Default")
      (node (ref "FR22") (pin "2") (pinfunction "2_2") (pintype "passive"))
      (node (ref "FR23") (pin "2") (pinfunction "2_2") (pintype "passive"))
      (node (ref "FR24") (pin "2") (pinfunction "2_2") (pintype "passive"))
      (node (ref "FR25") (pin "2") (pinfunction "2_2") (pintype "passive"))
    )
    (net (code "41") (name "VCC1P8_LMS") (class "Default")
      (node (ref "FR26") (pin "2") (pinfunction "2_2") (pintype "passive"))
      (node (ref "FR27") (pin "1") (pinfunction "1_1") (pintype "passive"))
      (node (ref "FR28") (pin "1") (pinfunction "1_1") (pintype "passive"))
      (node (ref "FR29") (pin "2") (pinfunction "2_2") (pintype "passive"))
      (node (ref "FR30") (pin "2") (pinfunction "2_2") (pintype "passive"))
      (node (ref "FR31") (pin "2") (pinfunction "2_2") (pintype "passive"))
      (node (ref "FR32") (pin "2") (pinfunction "2_2") (pintype "passive"))
      (node (ref "FR33") (pin "2") (pinfunction "2_2") (pintype "passive"))
      (node (ref "R68") (pin "2") (pinfunction "2_2") (pintype "passive"))
      (node (ref "R70") (pin "2") (pinfunction "2_2") (pintype "passive"))
      (node (ref "R71") (pin "1") (pinfunction "1_1") (pintype "passive"))
    )
    (net (code "42") (name "VCC1P25_LMS") (class "Default")
      (node (ref "FR10") (pin "2") (pinfunction "2_2") (pintype "passive"))
      (node (ref "FR11") (pin "2") (pinfunction "2_2") (pintype "passive"))
      (node (ref "FR12") (pin "2") (pinfunction "2_2") (pintype "passive"))
      (node (ref "FR13") (pin "2") (pinfunction "2_2") (pintype "passive"))
      (node (ref "FR14") (pin "2") (pinfunction "2_2") (pintype "passive"))
      (node (ref "FR15") (pin "2") (pinfunction "2_2") (pintype "passive"))
      (node (ref "FR16") (pin "2") (pinfunction "2_2") (pintype "passive"))
      (node (ref "FR17") (pin "2") (pinfunction "2_2") (pintype "passive"))
      (node (ref "FR18") (pin "2") (pinfunction "2_2") (pintype "passive"))
      (node (ref "FR19") (pin "2") (pinfunction "2_2") (pintype "passive"))
      (node (ref "FR20") (pin "2") (pinfunction "2_2") (pintype "passive"))
      (node (ref "FR21") (pin "2") (pinfunction "2_2") (pintype "passive"))
      (node (ref "FR5") (pin "2") (pinfunction "2_2") (pintype "passive"))
      (node (ref "FR6") (pin "2") (pinfunction "2_2") (pintype "passive"))
      (node (ref "FR7") (pin "2") (pinfunction "2_2") (pintype "passive"))
      (node (ref "FR8") (pin "2") (pinfunction "2_2") (pintype "passive"))
      (node (ref "FR9") (pin "2") (pinfunction "2_2") (pintype "passive"))
      (node (ref "R65") (pin "1") (pinfunction "1_1") (pintype "passive"))
    )
    (net (code "43") (name "VDIO_LMS") (class "Default")
      (node (ref "R69") (pin "1") (pinfunction "1_1") (pintype "passive"))
    )
  )
)
